# Power.net
KiCad netlist of a schematic drawn in Altium Designer
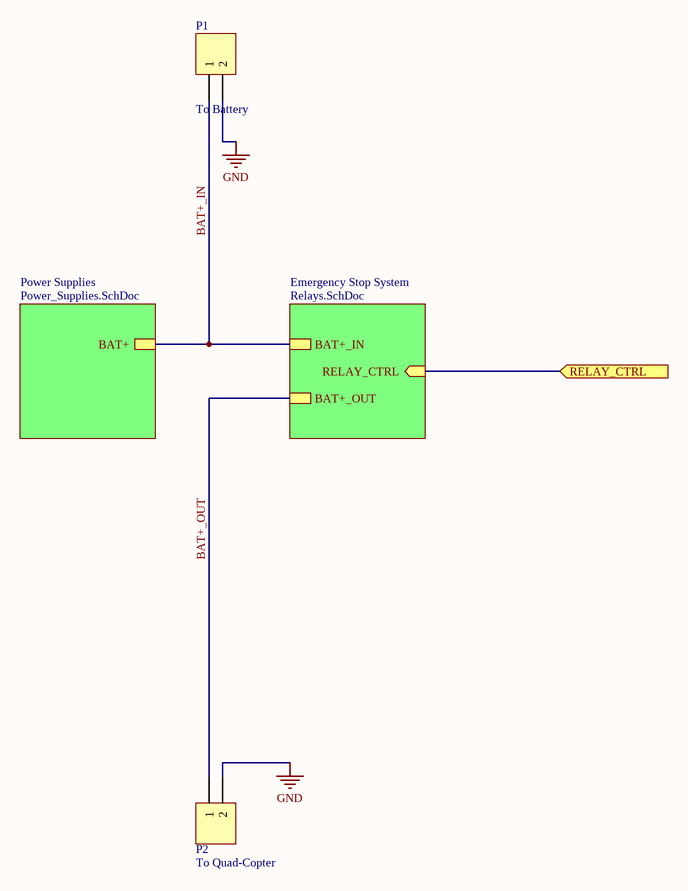
[diagram p0: Power.SchDoc]

(export (version "E")
  (design (tool "Eeschema 10.0.6"))
  (components
    (comp (ref "P1")
      (value "To Battery")
      (footprint "XT60")
      (description "XT60")
      (fields (field (name "MANUFACTURER PART NUMBER") "PRT-10474") (field (name "MANUFACTURER") "SparkFun"))
      (libsource (lib "") (part "Header 2_1"))
    )
    (comp (ref "P2")
      (value "To Quad-Copter")
      (footprint "XT60")
      (description "XT60")
      (fields (field (name "MANUFACTURER PART NUMBER") "PRT-10474") (field (name "MANUFACTURER") "SparkFun"))
      (libsource (lib "Miscellaneous Connectors") (part "Header 2"))
    )
  )
  (nets
    (net (code "1") (name "/BAT+_IN") (class "Default")
      (node (ref "P1") (pin "1") (pinfunction "1_1") (pintype "passive"))
    )
    (net (code "2") (name "/BAT+_OUT") (class "Default")
      (node (ref "P2") (pin "1") (pinfunction "1_1") (pintype "passive"))
    )
    (net (code "4") (name "GND") (class "Default")
      (node (ref "P1") (pin "2") (pinfunction "2_2") (pintype "passive"))
      (node (ref "P2") (pin "2") (pinfunction "2_2") (pintype "passive"))
    )
  )
)
